# WM8904_mikroBUS_04.net
KiCad netlist of a schematic drawn in EasyEDA Pro
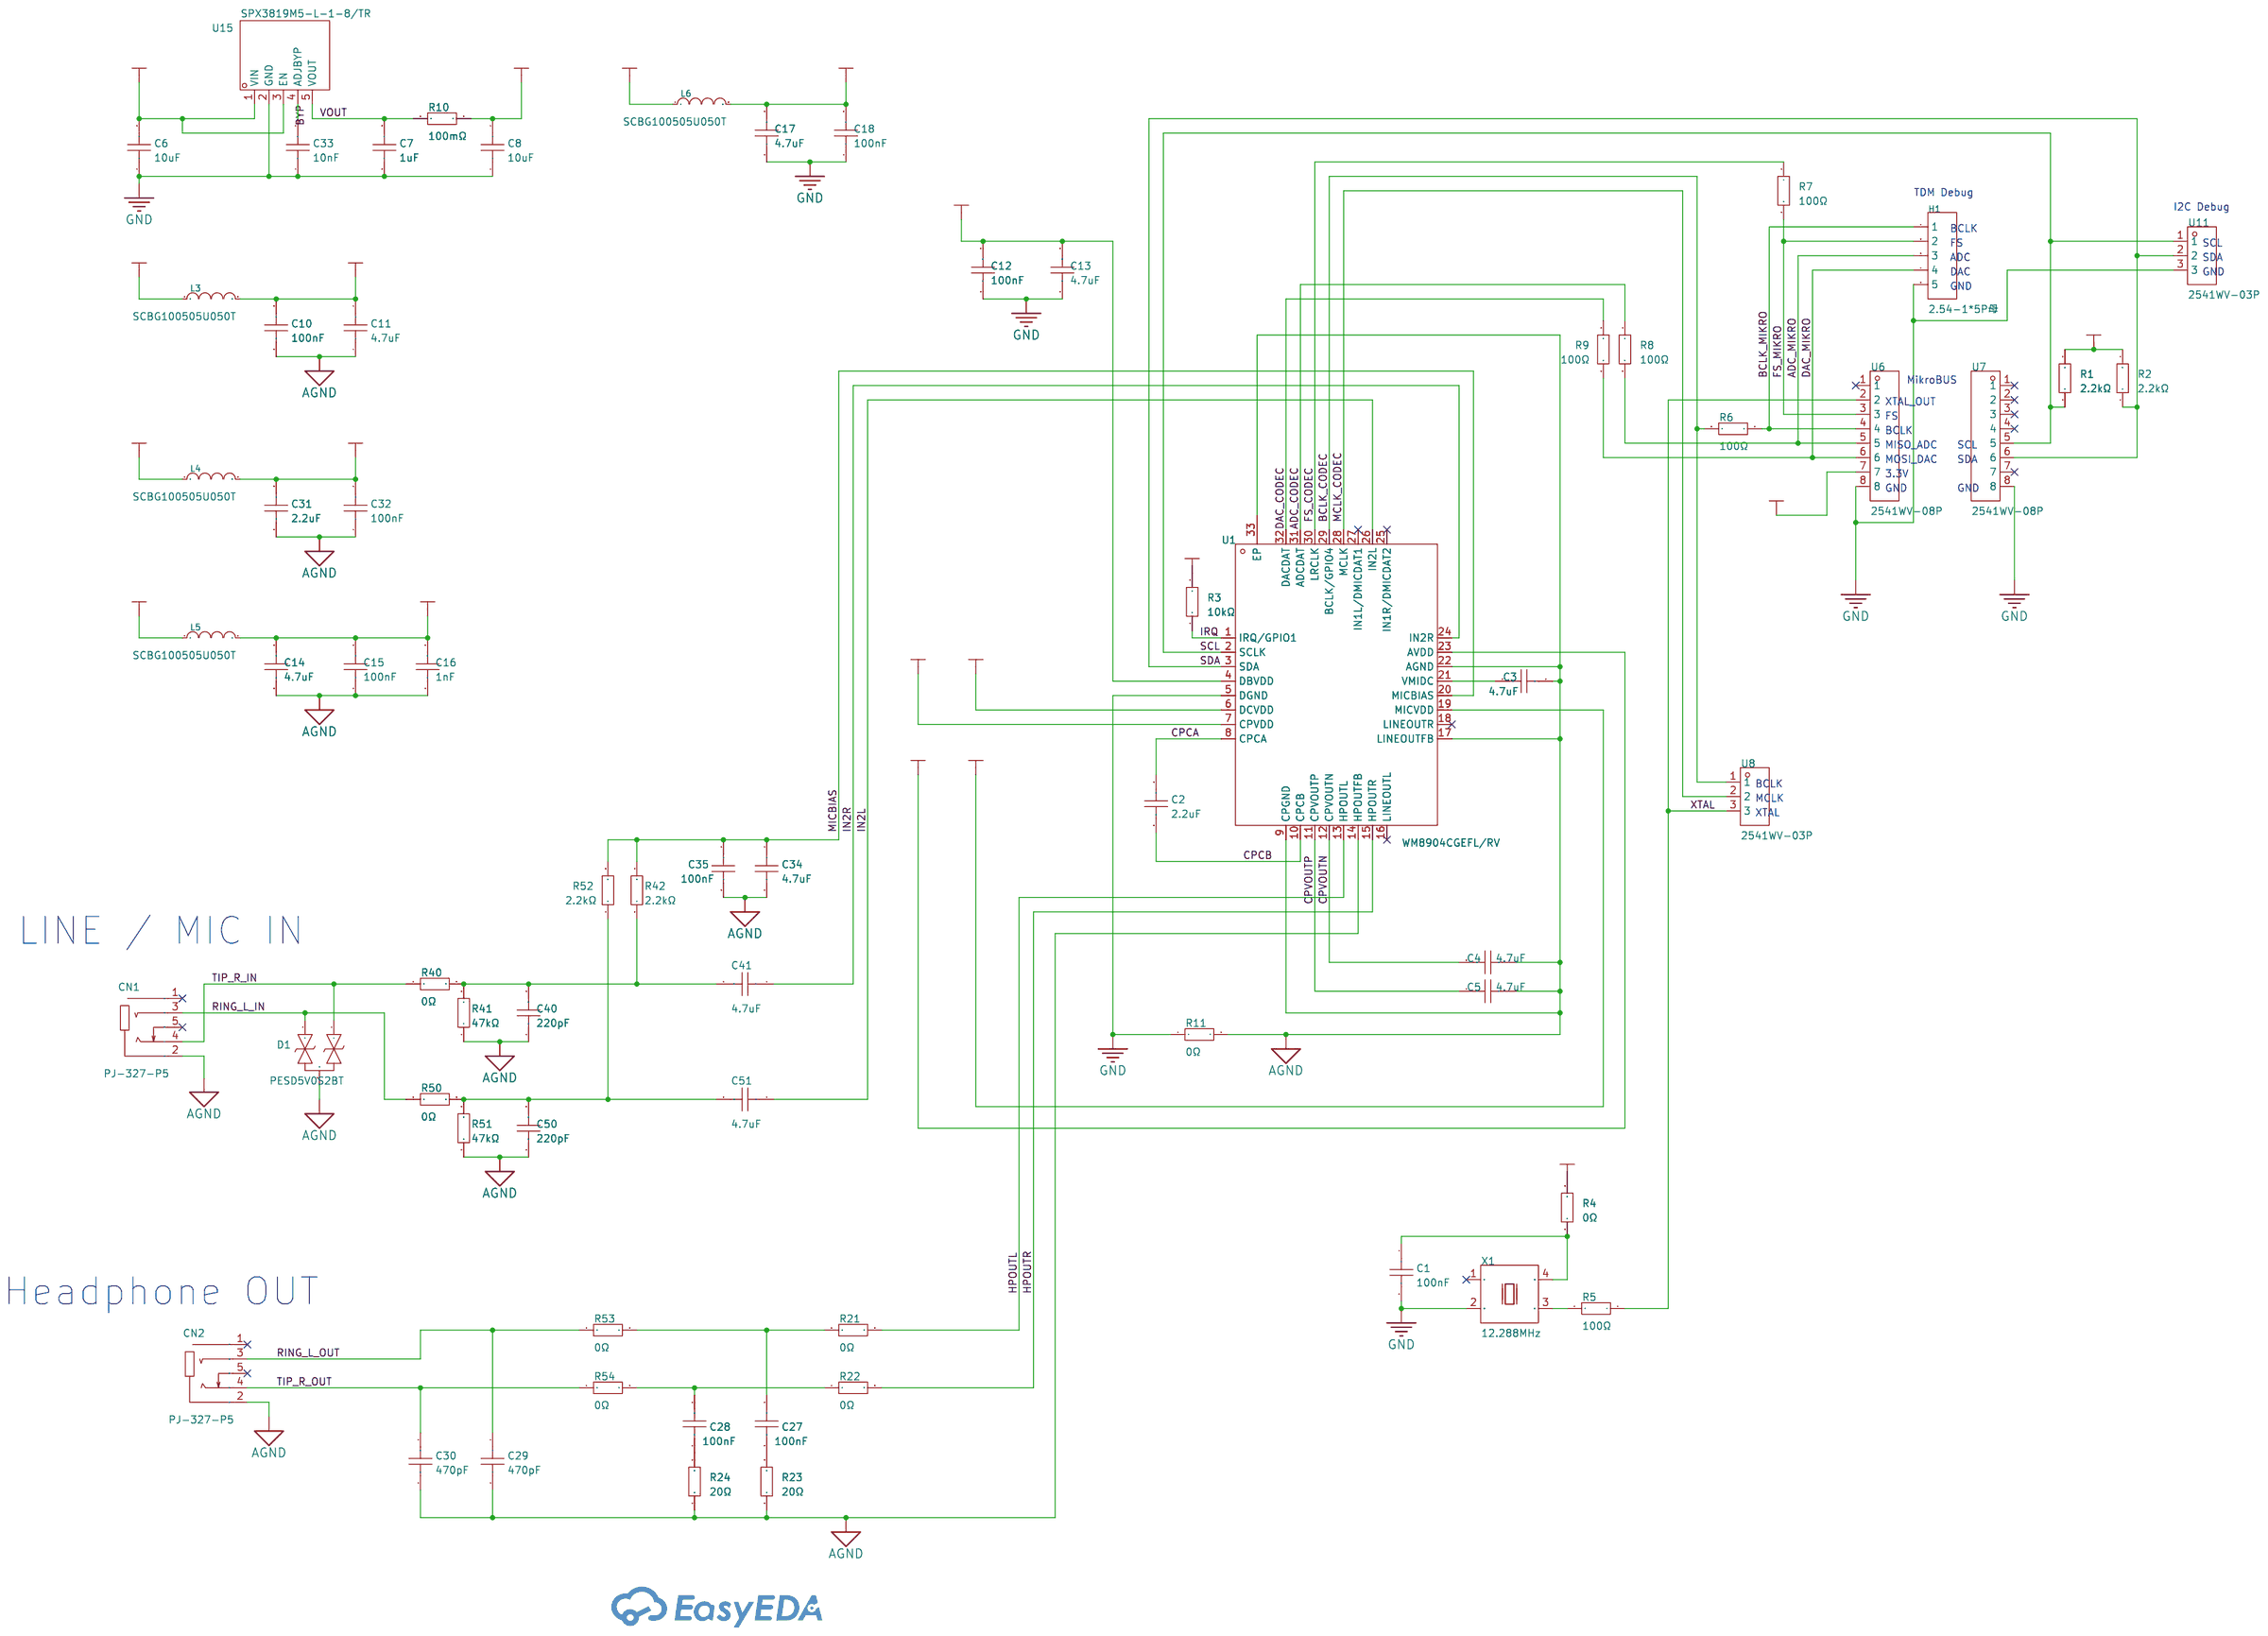
[diagram p0: schematic sheet]

(export (version "E")
  (design (tool "Eeschema 10.0.6"))
  (components
    (comp (ref "C1")
      (value "100nF")
      (footprint "easyedapro:C0603")
      (description "Capacitance:100nF Tolerance:±10% Tolerance:±10% Voltage Rating:50V Temperature Coefficient:X7R")
      (fields
        (field (name "Manufacturer Part") "CC0603KRX7R9BB104")
        (field (name "Manufacturer") "YAGEO(国巨)")
      )
      (libsource (lib "easyedapro") (part "CAP"))
    )
    (comp (ref "C2")
      (value "2.2uF")
      (footprint "easyedapro:C0603")
      (description "Capacitance:2.2uF Tolerance:±10% Tolerance:±10% Voltage Rating:16V Temperature Coefficient:X5R")
      (fields
        (field (name "Manufacturer Part") "CL10A225KO8NNNC")
        (field (name "Manufacturer") "SAMSUNG(三星)")
      )
      (libsource (lib "easyedapro") (part "CAP"))
    )
    (comp (ref "C3")
      (value "4.7uF")
      (footprint "easyedapro:C0603")
      (description "Capacitance:4.7uF Tolerance:±10% Tolerance:±10% Voltage Rating:16V Temperature Coefficient:X5R")
      (fields
        (field (name "Manufacturer Part") "CL10A475KO8NNNC")
        (field (name "Manufacturer") "SAMSUNG(三星)")
      )
      (libsource (lib "easyedapro") (part "CAP"))
    )
    (comp (ref "C4")
      (value "4.7uF")
      (footprint "easyedapro:C0603")
      (description "Capacitance:4.7uF Tolerance:±10% Tolerance:±10% Voltage Rating:16V Temperature Coefficient:X5R")
      (fields
        (field (name "Manufacturer Part") "CL10A475KO8NNNC")
        (field (name "Manufacturer") "SAMSUNG(三星)")
      )
      (libsource (lib "easyedapro") (part "CAP"))
    )
    (comp (ref "C5")
      (value "4.7uF")
      (footprint "easyedapro:C0603")
      (description "Capacitance:4.7uF Tolerance:±10% Tolerance:±10% Voltage Rating:16V Temperature Coefficient:X5R")
      (fields
        (field (name "Manufacturer Part") "CL10A475KO8NNNC")
        (field (name "Manufacturer") "SAMSUNG(三星)")
      )
      (libsource (lib "easyedapro") (part "CAP"))
    )
    (comp (ref "C6")
      (value "10uF")
      (footprint "easyedapro:C0603")
      (description "Capacitance:10uF Tolerance:±10% Tolerance:±10% Voltage Rating:10V Temperature Coefficient:X5R")
      (fields
        (field (name "Manufacturer Part") "CL10A106KP8NNNC")
        (field (name "Manufacturer") "SAMSUNG(三星)")
      )
      (libsource (lib "easyedapro") (part "CAP"))
    )
    (comp (ref "C7")
      (value "1uF")
      (footprint "easyedapro:C0603")
      (description "Capacitance:1uF Tolerance:±10% Tolerance:±10% Voltage Rating:50V Temperature Coefficient:X5R")
      (fields
        (field (name "Manufacturer Part") "CL10A105KB8NNNC")
        (field (name "Manufacturer") "SAMSUNG(三星)")
      )
      (libsource (lib "easyedapro") (part "CAP"))
    )
    (comp (ref "C8")
      (value "10uF")
      (footprint "easyedapro:C0603")
      (description "Capacitance:10uF Tolerance:±10% Tolerance:±10% Voltage Rating:10V Temperature Coefficient:X5R")
      (fields
        (field (name "Manufacturer Part") "CL10A106KP8NNNC")
        (field (name "Manufacturer") "SAMSUNG(三星)")
      )
      (libsource (lib "easyedapro") (part "CAP"))
    )
    (comp (ref "C10")
      (value "100nF")
      (footprint "easyedapro:C0603")
      (description "Capacitance:100nF Tolerance:±10% Tolerance:±10% Voltage Rating:50V Temperature Coefficient:X7R")
      (fields
        (field (name "Manufacturer Part") "CC0603KRX7R9BB104")
        (field (name "Manufacturer") "YAGEO(国巨)")
      )
      (libsource (lib "easyedapro") (part "CAP"))
    )
    (comp (ref "C11")
      (value "4.7uF")
      (footprint "easyedapro:C0603")
      (description "Capacitance:4.7uF Tolerance:±10% Tolerance:±10% Voltage Rating:16V Temperature Coefficient:X5R")
      (fields
        (field (name "Manufacturer Part") "CL10A475KO8NNNC")
        (field (name "Manufacturer") "SAMSUNG(三星)")
      )
      (libsource (lib "easyedapro") (part "CAP"))
    )
    (comp (ref "C12")
      (value "100nF")
      (footprint "easyedapro:C0603")
      (description "Capacitance:100nF Tolerance:±10% Tolerance:±10% Voltage Rating:50V Temperature Coefficient:X7R")
      (fields
        (field (name "Manufacturer Part") "CC0603KRX7R9BB104")
        (field (name "Manufacturer") "YAGEO(国巨)")
      )
      (libsource (lib "easyedapro") (part "CAP"))
    )
    (comp (ref "C13")
      (value "4.7uF")
      (footprint "easyedapro:C0603")
      (description "Capacitance:4.7uF Tolerance:±10% Tolerance:±10% Voltage Rating:16V Temperature Coefficient:X5R")
      (fields
        (field (name "Manufacturer Part") "CL10A475KO8NNNC")
        (field (name "Manufacturer") "SAMSUNG(三星)")
      )
      (libsource (lib "easyedapro") (part "CAP"))
    )
    (comp (ref "C14")
      (value "4.7uF")
      (footprint "easyedapro:C0603")
      (description "Capacitance:4.7uF Tolerance:±10% Tolerance:±10% Voltage Rating:16V Temperature Coefficient:X5R")
      (fields
        (field (name "Manufacturer Part") "CL10A475KO8NNNC")
        (field (name "Manufacturer") "SAMSUNG(三星)")
      )
      (libsource (lib "easyedapro") (part "CAP"))
    )
    (comp (ref "C15")
      (value "100nF")
      (footprint "easyedapro:C0603")
      (description "Capacitance:100nF Tolerance:±10% Tolerance:±10% Voltage Rating:50V Temperature Coefficient:X7R")
      (fields
        (field (name "Manufacturer Part") "CC0603KRX7R9BB104")
        (field (name "Manufacturer") "YAGEO(国巨)")
      )
      (libsource (lib "easyedapro") (part "CAP"))
    )
    (comp (ref "C16")
      (value "1nF")
      (footprint "easyedapro:C0603")
      (description "Capacitance:1nF Tolerance:±10% Tolerance:±10% Voltage Rating:50V Temperature Coefficient:X7R")
      (fields
        (field (name "Manufacturer Part") "CL10B102KB8NNNC")
        (field (name "Manufacturer") "SAMSUNG(三星)")
      )
      (libsource (lib "easyedapro") (part "CAP"))
    )
    (comp (ref "C17")
      (value "4.7uF")
      (footprint "easyedapro:C0603")
      (description "Capacitance:4.7uF Tolerance:±10% Tolerance:±10% Voltage Rating:16V Temperature Coefficient:X5R")
      (fields
        (field (name "Manufacturer Part") "CL10A475KO8NNNC")
        (field (name "Manufacturer") "SAMSUNG(三星)")
      )
      (libsource (lib "easyedapro") (part "CAP"))
    )
    (comp (ref "C18")
      (value "100nF")
      (footprint "easyedapro:C0603")
      (description "Capacitance:100nF Tolerance:±10% Tolerance:±10% Voltage Rating:50V Temperature Coefficient:X7R")
      (fields
        (field (name "Manufacturer Part") "CC0603KRX7R9BB104")
        (field (name "Manufacturer") "YAGEO(国巨)")
      )
      (libsource (lib "easyedapro") (part "CAP"))
    )
    (comp (ref "C27")
      (value "100nF")
      (footprint "easyedapro:C0603")
      (description "Capacitance:100nF Tolerance:±10% Tolerance:±10% Voltage Rating:50V Temperature Coefficient:X7R")
      (fields
        (field (name "Manufacturer Part") "CC0603KRX7R9BB104")
        (field (name "Manufacturer") "YAGEO(国巨)")
      )
      (libsource (lib "easyedapro") (part "CAP"))
    )
    (comp (ref "C28")
      (value "100nF")
      (footprint "easyedapro:C0603")
      (description "Capacitance:100nF Tolerance:±10% Tolerance:±10% Voltage Rating:50V Temperature Coefficient:X7R")
      (fields
        (field (name "Manufacturer Part") "CC0603KRX7R9BB104")
        (field (name "Manufacturer") "YAGEO(国巨)")
      )
      (libsource (lib "easyedapro") (part "CAP"))
    )
    (comp (ref "C29")
      (value "470pF")
      (footprint "easyedapro:C0603")
      (description "Capacitance:470pF Tolerance:±10% Tolerance:±10% Voltage Rating:50V Temperature Coefficient:X7R")
      (fields (field (name "Manufacturer Part") "0603B471K500NT") (field (name "Manufacturer") "FH(风华)"))
      (libsource (lib "easyedapro") (part "CAP"))
    )
    (comp (ref "C30")
      (value "470pF")
      (footprint "easyedapro:C0603")
      (description "Capacitance:470pF Tolerance:±10% Tolerance:±10% Voltage Rating:50V Temperature Coefficient:X7R")
      (fields (field (name "Manufacturer Part") "0603B471K500NT") (field (name "Manufacturer") "FH(风华)"))
      (libsource (lib "easyedapro") (part "CAP"))
    )
    (comp (ref "C31")
      (value "2.2uF")
      (footprint "easyedapro:C0603")
      (description "Capacitance:2.2uF Tolerance:±10% Tolerance:±10% Voltage Rating:16V Temperature Coefficient:X5R")
      (fields
        (field (name "Manufacturer Part") "CL10A225KO8NNNC")
        (field (name "Manufacturer") "SAMSUNG(三星)")
      )
      (libsource (lib "easyedapro") (part "CAP"))
    )
    (comp (ref "C32")
      (value "100nF")
      (footprint "easyedapro:C0603")
      (description "Capacitance:100nF Tolerance:±10% Tolerance:±10% Voltage Rating:50V Temperature Coefficient:X7R")
      (fields
        (field (name "Manufacturer Part") "CC0603KRX7R9BB104")
        (field (name "Manufacturer") "YAGEO(国巨)")
      )
      (libsource (lib "easyedapro") (part "CAP"))
    )
    (comp (ref "C33")
      (value "10nF")
      (footprint "easyedapro:C0603")
      (description "Capacitance:10nF Tolerance:±10% Tolerance:±10% Voltage Rating:50V Temperature Coefficient:X7R")
      (fields (field (name "Manufacturer Part") "0603B103K500NT") (field (name "Manufacturer") "FH(风华)"))
      (libsource (lib "easyedapro") (part "CAP"))
    )
    (comp (ref "C34")
      (value "4.7uF")
      (footprint "easyedapro:C0603")
      (description "Capacitance:4.7uF Tolerance:±10% Tolerance:±10% Voltage Rating:16V Temperature Coefficient:X5R")
      (fields
        (field (name "Manufacturer Part") "CL10A475KO8NNNC")
        (field (name "Manufacturer") "SAMSUNG(三星)")
      )
      (libsource (lib "easyedapro") (part "CAP"))
    )
    (comp (ref "C35")
      (value "100nF")
      (footprint "easyedapro:C0603")
      (description "Capacitance:100nF Tolerance:±10% Tolerance:±10% Voltage Rating:50V Temperature Coefficient:X7R")
      (fields
        (field (name "Manufacturer Part") "CC0603KRX7R9BB104")
        (field (name "Manufacturer") "YAGEO(国巨)")
      )
      (libsource (lib "easyedapro") (part "CAP"))
    )
    (comp (ref "C40")
      (value "220pF")
      (footprint "easyedapro:C0603")
      (description "Capacitance:220pF Tolerance:±10% Tolerance:±10% Voltage Rating:50V Temperature Coefficient:X7R")
      (fields
        (field (name "Manufacturer Part") "CL10B221KB8NNNC")
        (field (name "Manufacturer") "SAMSUNG(三星)")
      )
      (libsource (lib "easyedapro") (part "CAP"))
    )
    (comp (ref "C41")
      (value "4.7uF")
      (footprint "easyedapro:C0603")
      (description "Capacitance:4.7uF Tolerance:±10% Tolerance:±10% Voltage Rating:16V Temperature Coefficient:X5R")
      (fields
        (field (name "Manufacturer Part") "CL10A475KO8NNNC")
        (field (name "Manufacturer") "SAMSUNG(三星)")
      )
      (libsource (lib "easyedapro") (part "CAP"))
    )
    (comp (ref "C50")
      (value "220pF")
      (footprint "easyedapro:C0603")
      (description "Capacitance:220pF Tolerance:±10% Tolerance:±10% Voltage Rating:50V Temperature Coefficient:X7R")
      (fields
        (field (name "Manufacturer Part") "CL10B221KB8NNNC")
        (field (name "Manufacturer") "SAMSUNG(三星)")
      )
      (libsource (lib "easyedapro") (part "CAP"))
    )
    (comp (ref "C51")
      (value "4.7uF")
      (footprint "easyedapro:C0603")
      (description "Capacitance:4.7uF Tolerance:±10% Tolerance:±10% Voltage Rating:16V Temperature Coefficient:X5R")
      (fields
        (field (name "Manufacturer Part") "CL10A475KO8NNNC")
        (field (name "Manufacturer") "SAMSUNG(三星)")
      )
      (libsource (lib "easyedapro") (part "CAP"))
    )
    (comp (ref "CN1")
      (value "PJ-327-P5")
      (footprint "easyedapro:AUDIO-TH_PJ-327-P5")
      (fields (field (name "Manufacturer") "SOFNG(硕方)"))
      (libsource (lib "easyedapro") (part "PJ-327-P5"))
    )
    (comp (ref "CN2")
      (value "PJ-327-P5")
      (footprint "easyedapro:AUDIO-TH_PJ-327-P5")
      (fields (field (name "Manufacturer") "SOFNG(硕方)"))
      (libsource (lib "easyedapro") (part "PJ-327-P5"))
    )
    (comp (ref "D1")
      (value "PESD5V0S2BT")
      (footprint "easyedapro:SOT-23-3_L2.9-W1.3-P1.90-LS2.4-BR")
      (fields (field (name "Manufacturer") "GOODWORK(固得沃克)"))
      (libsource (lib "easyedapro") (part "PESD5V0S2BT_C28310457"))
    )
    (comp (ref "H1")
      (value "2.54-1*5P母")
      (footprint "easyedapro:HDR-TH_5P-P2.54-V-F")
      (fields (field (name "Manufacturer") "BOOMELE(博穆精密)"))
      (libsource (lib "easyedapro") (part "Header-Female-2.54_1x5"))
    )
    (comp (ref "L3")
      (value "SCBG100505U050T")
      (footprint "easyedapro:L0402")
      (fields (field (name "Manufacturer") "Yanchuang(研创)"))
      (libsource (lib "easyedapro") (part "SCBG100505U050T"))
    )
    (comp (ref "L4")
      (value "SCBG100505U050T")
      (footprint "easyedapro:L0402")
      (fields (field (name "Manufacturer") "Yanchuang(研创)"))
      (libsource (lib "easyedapro") (part "SCBG100505U050T"))
    )
    (comp (ref "L5")
      (value "SCBG100505U050T")
      (footprint "easyedapro:L0402")
      (fields (field (name "Manufacturer") "Yanchuang(研创)"))
      (libsource (lib "easyedapro") (part "SCBG100505U050T"))
    )
    (comp (ref "L6")
      (value "SCBG100505U050T")
      (footprint "easyedapro:L0402")
      (fields (field (name "Manufacturer") "Yanchuang(研创)"))
      (libsource (lib "easyedapro") (part "SCBG100505U050T"))
    )
    (comp (ref "R1")
      (value "2.2kΩ")
      (footprint "easyedapro:R0603")
      (fields
        (field (name "Manufacturer Part") "0603WAF2201T5E")
        (field (name "Manufacturer") "UNI-ROYAL(厚声)")
      )
      (libsource (lib "easyedapro") (part "Res"))
    )
    (comp (ref "R2")
      (value "2.2kΩ")
      (footprint "easyedapro:R0603")
      (fields
        (field (name "Manufacturer Part") "0603WAF2201T5E")
        (field (name "Manufacturer") "UNI-ROYAL(厚声)")
      )
      (libsource (lib "easyedapro") (part "Res"))
    )
    (comp (ref "R3")
      (value "10kΩ")
      (footprint "easyedapro:R0603")
      (fields
        (field (name "Manufacturer Part") "0603WAF1002T5E")
        (field (name "Manufacturer") "UNI-ROYAL(厚声)")
      )
      (libsource (lib "easyedapro") (part "Res"))
    )
    (comp (ref "R4")
      (value "0Ω")
      (footprint "easyedapro:R0603")
      (fields
        (field (name "Manufacturer Part") "0603WAF0000T5E")
        (field (name "Manufacturer") "UNI-ROYAL(厚声)")
      )
      (libsource (lib "easyedapro") (part "Res"))
    )
    (comp (ref "R5")
      (value "100Ω")
      (footprint "easyedapro:R0603")
      (fields
        (field (name "Manufacturer Part") "0603WAF1000T5E")
        (field (name "Manufacturer") "UNI-ROYAL(厚声)")
      )
      (libsource (lib "easyedapro") (part "Res"))
    )
    (comp (ref "R6")
      (value "100Ω")
      (footprint "easyedapro:R0603")
      (fields
        (field (name "Manufacturer Part") "0603WAF1000T5E")
        (field (name "Manufacturer") "UNI-ROYAL(厚声)")
      )
      (libsource (lib "easyedapro") (part "Res"))
    )
    (comp (ref "R7")
      (value "100Ω")
      (footprint "easyedapro:R0603")
      (fields
        (field (name "Manufacturer Part") "0603WAF1000T5E")
        (field (name "Manufacturer") "UNI-ROYAL(厚声)")
      )
      (libsource (lib "easyedapro") (part "Res"))
    )
    (comp (ref "R8")
      (value "100Ω")
      (footprint "easyedapro:R0603")
      (fields
        (field (name "Manufacturer Part") "0603WAF1000T5E")
        (field (name "Manufacturer") "UNI-ROYAL(厚声)")
      )
      (libsource (lib "easyedapro") (part "Res"))
    )
    (comp (ref "R9")
      (value "100Ω")
      (footprint "easyedapro:R0603")
      (fields
        (field (name "Manufacturer Part") "0603WAF1000T5E")
        (field (name "Manufacturer") "UNI-ROYAL(厚声)")
      )
      (libsource (lib "easyedapro") (part "Res"))
    )
    (comp (ref "R10")
      (value "100mΩ")
      (footprint "easyedapro:R0603")
      (fields
        (field (name "Manufacturer Part") "0603WAJ010KT5E")
        (field (name "Manufacturer") "UNI-ROYAL(厚声)")
      )
      (libsource (lib "easyedapro") (part "Res"))
    )
    (comp (ref "R11")
      (value "0Ω")
      (footprint "easyedapro:R0603")
      (fields
        (field (name "Manufacturer Part") "0603WAF0000T5E")
        (field (name "Manufacturer") "UNI-ROYAL(厚声)")
      )
      (libsource (lib "easyedapro") (part "Res"))
    )
    (comp (ref "R21")
      (value "0Ω")
      (footprint "easyedapro:R0603")
      (fields
        (field (name "Manufacturer Part") "0603WAF0000T5E")
        (field (name "Manufacturer") "UNI-ROYAL(厚声)")
      )
      (libsource (lib "easyedapro") (part "Res"))
    )
    (comp (ref "R22")
      (value "0Ω")
      (footprint "easyedapro:R0603")
      (fields
        (field (name "Manufacturer Part") "0603WAF0000T5E")
        (field (name "Manufacturer") "UNI-ROYAL(厚声)")
      )
      (libsource (lib "easyedapro") (part "Res"))
    )
    (comp (ref "R23")
      (value "20Ω")
      (footprint "easyedapro:R0603")
      (fields
        (field (name "Manufacturer Part") "0603WAF200JT5E")
        (field (name "Manufacturer") "UNI-ROYAL(厚声)")
      )
      (libsource (lib "easyedapro") (part "Res"))
    )
    (comp (ref "R24")
      (value "20Ω")
      (footprint "easyedapro:R0603")
      (fields
        (field (name "Manufacturer Part") "0603WAF200JT5E")
        (field (name "Manufacturer") "UNI-ROYAL(厚声)")
      )
      (libsource (lib "easyedapro") (part "Res"))
    )
    (comp (ref "R40")
      (value "0Ω")
      (footprint "easyedapro:R0603")
      (fields
        (field (name "Manufacturer Part") "0603WAF0000T5E")
        (field (name "Manufacturer") "UNI-ROYAL(厚声)")
      )
      (libsource (lib "easyedapro") (part "Res"))
    )
    (comp (ref "R41")
      (value "47kΩ")
      (footprint "easyedapro:R0603")
      (fields
        (field (name "Manufacturer Part") "0603WAF4702T5E")
        (field (name "Manufacturer") "UNI-ROYAL(厚声)")
      )
      (libsource (lib "easyedapro") (part "Res"))
    )
    (comp (ref "R42")
      (value "2.2kΩ")
      (footprint "easyedapro:R0603")
      (fields
        (field (name "Manufacturer Part") "0603WAF2201T5E")
        (field (name "Manufacturer") "UNI-ROYAL(厚声)")
      )
      (libsource (lib "easyedapro") (part "Res"))
    )
    (comp (ref "R50")
      (value "0Ω")
      (footprint "easyedapro:R0603")
      (fields
        (field (name "Manufacturer Part") "0603WAF0000T5E")
        (field (name "Manufacturer") "UNI-ROYAL(厚声)")
      )
      (libsource (lib "easyedapro") (part "Res"))
    )
    (comp (ref "R51")
      (value "47kΩ")
      (footprint "easyedapro:R0603")
      (fields
        (field (name "Manufacturer Part") "0603WAF4702T5E")
        (field (name "Manufacturer") "UNI-ROYAL(厚声)")
      )
      (libsource (lib "easyedapro") (part "Res"))
    )
    (comp (ref "R52")
      (value "2.2kΩ")
      (footprint "easyedapro:R0603")
      (fields
        (field (name "Manufacturer Part") "0603WAF2201T5E")
        (field (name "Manufacturer") "UNI-ROYAL(厚声)")
      )
      (libsource (lib "easyedapro") (part "Res"))
    )
    (comp (ref "R53")
      (value "0Ω")
      (footprint "easyedapro:R0603")
      (fields
        (field (name "Manufacturer Part") "0603WAF0000T5E")
        (field (name "Manufacturer") "UNI-ROYAL(厚声)")
      )
      (libsource (lib "easyedapro") (part "Res"))
    )
    (comp (ref "R54")
      (value "0Ω")
      (footprint "easyedapro:R0603")
      (fields
        (field (name "Manufacturer Part") "0603WAF0000T5E")
        (field (name "Manufacturer") "UNI-ROYAL(厚声)")
      )
      (libsource (lib "easyedapro") (part "Res"))
    )
    (comp (ref "U1")
      (value "WM8904CGEFL/RV")
      (footprint "easyedapro:QFN-32_L4.0-W4.0-P0.40-BL-EP2.7")
      (fields (field (name "Manufacturer") "Cirrus Logic(凌云)"))
      (libsource (lib "easyedapro") (part "WM8904CGEFL/RV"))
    )
    (comp (ref "U6")
      (value "2541WV-08P")
      (footprint "easyedapro:HDR-TH_8P-P2.54-V-M-4")
      (fields (field (name "Manufacturer") "HanElectricity(瀚源)"))
      (libsource (lib "easyedapro") (part "2541WV-08P"))
    )
    (comp (ref "U7")
      (value "2541WV-08P")
      (footprint "easyedapro:HDR-TH_8P-P2.54-V-M-4")
      (fields (field (name "Manufacturer") "HanElectricity(瀚源)"))
      (libsource (lib "easyedapro") (part "2541WV-08P"))
    )
    (comp (ref "U8")
      (value "2541WV-03P")
      (footprint "easyedapro:HDR-TH_3P-P2.54-V-M-2")
      (fields (field (name "Manufacturer") "HanElectricity(瀚源)"))
      (libsource (lib "easyedapro") (part "2541WV-03P"))
    )
    (comp (ref "U11")
      (value "2541WV-03P")
      (footprint "easyedapro:HDR-TH_3P-P2.54-V-M-2")
      (fields (field (name "Manufacturer") "HanElectricity(瀚源)"))
      (libsource (lib "easyedapro") (part "2541WV-03P"))
    )
    (comp (ref "U15")
      (value "SPX3819M5-L-1-8/TR")
      (footprint "easyedapro:SOT-23-5_L3.0-W1.7-P0.95-LS2.8-TL")
      (fields (field (name "Manufacturer") "MaxLinear(迈凌)"))
      (libsource (lib "easyedapro") (part "SPX3819M5-L-1-8"))
    )
    (comp (ref "X1")
      (value "12.288MHz")
      (footprint "easyedapro:OSC-SMD_4P-L2.5-W2.0-BL")
      (fields (field (name "Manufacturer Part") "X1G0041710019") (field (name "Manufacturer") "EPSON(爱普生)"))
      (libsource (lib "easyedapro") (part "X1G004171001900"))
    )
  )
  (nets
    (net (code "1") (name "+3.3V") (class "Default")
      (node (ref "C12") (pin "2") (pinfunction "2_2") (pintype "input"))
      (node (ref "C13") (pin "2") (pinfunction "2_2") (pintype "input"))
      (node (ref "C6") (pin "2") (pinfunction "2_2") (pintype "input"))
      (node (ref "L3") (pin "1") (pinfunction "1_1") (pintype "input"))
      (node (ref "R1") (pin "2") (pinfunction "2_2") (pintype "input"))
      (node (ref "R2") (pin "2") (pinfunction "2_2") (pintype "input"))
      (node (ref "R3") (pin "2") (pinfunction "2_2") (pintype "input"))
      (node (ref "R4") (pin "2") (pinfunction "2_2") (pintype "input"))
      (node (ref "U1") (pin "4") (pinfunction "DBVDD_4") (pintype "unspecified"))
      (node (ref "U15") (pin "1") (pinfunction "VIN_1") (pintype "unspecified"))
      (node (ref "U15") (pin "3") (pinfunction "EN_3") (pintype "unspecified"))
      (node (ref "U6") (pin "7") (pinfunction "7_7") (pintype "unspecified"))
    )
    (net (code "2") (name "/ADC_CODEC") (class "Default")
      (node (ref "R8") (pin "1") (pinfunction "1_1") (pintype "input"))
      (node (ref "U1") (pin "31") (pinfunction "ADCDAT_31") (pintype "unspecified"))
    )
    (net (code "3") (name "/ADC_MIKRO") (class "Default")
      (node (ref "H1") (pin "3") (pinfunction "3_3") (pintype "input"))
      (node (ref "R8") (pin "2") (pinfunction "2_2") (pintype "input"))
      (node (ref "U6") (pin "5") (pinfunction "5_5") (pintype "unspecified"))
    )
    (net (code "4") (name "/BCLK_CODEC") (class "Default")
      (node (ref "R6") (pin "2") (pinfunction "2_2") (pintype "input"))
      (node (ref "U1") (pin "29") (pinfunction "BCLK/GPIO4_29") (pintype "unspecified"))
      (node (ref "U8") (pin "1") (pinfunction "1_1") (pintype "unspecified"))
    )
    (net (code "5") (name "/BCLK_MIKRO") (class "Default")
      (node (ref "H1") (pin "1") (pinfunction "1_1") (pintype "input"))
      (node (ref "R6") (pin "1") (pinfunction "1_1") (pintype "input"))
      (node (ref "U6") (pin "4") (pinfunction "4_4") (pintype "unspecified"))
    )
    (net (code "6") (name "/BYP") (class "Default")
      (node (ref "C33") (pin "2") (pinfunction "2_2") (pintype "input"))
      (node (ref "U15") (pin "4") (pinfunction "ADJBYP_4") (pintype "unspecified"))
    )
    (net (code "7") (name "/CPCA") (class "Default")
      (node (ref "C2") (pin "1") (pinfunction "1_1") (pintype "input"))
      (node (ref "U1") (pin "8") (pinfunction "CPCA_8") (pintype "unspecified"))
    )
    (net (code "8") (name "/CPCB") (class "Default")
      (node (ref "C2") (pin "2") (pinfunction "2_2") (pintype "input"))
      (node (ref "U1") (pin "10") (pinfunction "CPCB_10") (pintype "unspecified"))
    )
    (net (code "9") (name "/CPVOUTN") (class "Default")
      (node (ref "C4") (pin "2") (pinfunction "2_2") (pintype "input"))
      (node (ref "U1") (pin "12") (pinfunction "CPVOUTN_12") (pintype "unspecified"))
    )
    (net (code "10") (name "/CPVOUTP") (class "Default")
      (node (ref "C5") (pin "2") (pinfunction "2_2") (pintype "input"))
      (node (ref "U1") (pin "11") (pinfunction "CPVOUTP_11") (pintype "unspecified"))
    )
    (net (code "11") (name "/DAC_CODEC") (class "Default")
      (node (ref "R9") (pin "1") (pinfunction "1_1") (pintype "input"))
      (node (ref "U1") (pin "32") (pinfunction "DACDAT_32") (pintype "unspecified"))
    )
    (net (code "12") (name "/DAC_MIKRO") (class "Default")
      (node (ref "H1") (pin "4") (pinfunction "4_4") (pintype "input"))
      (node (ref "R9") (pin "2") (pinfunction "2_2") (pintype "input"))
      (node (ref "U6") (pin "6") (pinfunction "6_6") (pintype "unspecified"))
    )
    (net (code "13") (name "/FS_CODEC") (class "Default")
      (node (ref "R7") (pin "1") (pinfunction "1_1") (pintype "input"))
      (node (ref "U1") (pin "30") (pinfunction "LRCLK_30") (pintype "unspecified"))
    )
    (net (code "14") (name "/FS_MIKRO") (class "Default")
      (node (ref "H1") (pin "2") (pinfunction "2_2") (pintype "input"))
      (node (ref "R7") (pin "2") (pinfunction "2_2") (pintype "input"))
      (node (ref "U6") (pin "3") (pinfunction "3_3") (pintype "unspecified"))
    )
    (net (code "15") (name "/HPOUTL") (class "Default")
      (node (ref "R21") (pin "2") (pinfunction "2_2") (pintype "input"))
      (node (ref "U1") (pin "13") (pinfunction "HPOUTL_13") (pintype "unspecified"))
    )
    (net (code "16") (name "/HPOUTR") (class "Default")
      (node (ref "R22") (pin "2") (pinfunction "2_2") (pintype "input"))
      (node (ref "U1") (pin "15") (pinfunction "HPOUTR_15") (pintype "unspecified"))
    )
    (net (code "17") (name "/IN2L") (class "Default")
      (node (ref "C51") (pin "1") (pinfunction "1_1") (pintype "input"))
      (node (ref "U1") (pin "26") (pinfunction "IN2L_26") (pintype "unspecified"))
    )
    (net (code "18") (name "/IN2R") (class "Default")
      (node (ref "C41") (pin "1") (pinfunction "1_1") (pintype "input"))
      (node (ref "U1") (pin "24") (pinfunction "IN2R_24") (pintype "unspecified"))
    )
    (net (code "19") (name "/IRQ") (class "Default")
      (node (ref "R3") (pin "1") (pinfunction "1_1") (pintype "input"))
      (node (ref "U1") (pin "1") (pinfunction "IRQ/GPIO1_1") (pintype "unspecified"))
    )
    (net (code "20") (name "/MCLK_CODEC") (class "Default")
      (node (ref "U1") (pin "28") (pinfunction "MCLK_28") (pintype "unspecified"))
      (node (ref "U8") (pin "2") (pinfunction "2_2") (pintype "unspecified"))
    )
    (net (code "21") (name "/MICBIAS") (class "Default")
      (node (ref "C34") (pin "1") (pinfunction "1_1") (pintype "input"))
      (node (ref "C35") (pin "1") (pinfunction "1_1") (pintype "input"))
      (node (ref "R42") (pin "2") (pinfunction "2_2") (pintype "input"))
      (node (ref "R52") (pin "2") (pinfunction "2_2") (pintype "input"))
      (node (ref "U1") (pin "20") (pinfunction "MICBIAS_20") (pintype "unspecified"))
    )
    (net (code "22") (name "/RING_L_IN") (class "Default")
      (node (ref "CN1") (pin "3") (pinfunction "3_3") (pintype "unspecified"))
      (node (ref "D1") (pin "2") (pinfunction "2_2") (pintype "unspecified"))
      (node (ref "R50") (pin "1") (pinfunction "1_1") (pintype "input"))
    )
    (net (code "23") (name "/RING_L_OUT") (class "Default")
      (node (ref "C29") (pin "1") (pinfunction "1_1") (pintype "input"))
      (node (ref "CN2") (pin "3") (pinfunction "3_3") (pintype "unspecified"))
      (node (ref "R53") (pin "1") (pinfunction "1_1") (pintype "input"))
    )
    (net (code "24") (name "/SCL") (class "Default")
      (node (ref "R1") (pin "1") (pinfunction "1_1") (pintype "input"))
      (node (ref "U1") (pin "2") (pinfunction "SCLK_2") (pintype "unspecified"))
      (node (ref "U11") (pin "1") (pinfunction "1_1") (pintype "unspecified"))
      (node (ref "U7") (pin "5") (pinfunction "5_5") (pintype "unspecified"))
    )
    (net (code "25") (name "/SDA") (class "Default")
      (node (ref "R2") (pin "1") (pinfunction "1_1") (pintype "input"))
      (node (ref "U1") (pin "3") (pinfunction "SDA_3") (pintype "unspecified"))
      (node (ref "U11") (pin "2") (pinfunction "2_2") (pintype "unspecified"))
      (node (ref "U7") (pin "6") (pinfunction "6_6") (pintype "unspecified"))
    )
    (net (code "26") (name "/TIP_R_IN") (class "Default")
      (node (ref "CN1") (pin "4") (pinfunction "4_4") (pintype "unspecified"))
      (node (ref "D1") (pin "1") (pinfunction "1_1") (pintype "unspecified"))
      (node (ref "R40") (pin "1") (pinfunction "1_1") (pintype "input"))
    )
    (net (code "27") (name "/TIP_R_OUT") (class "Default")
      (node (ref "C30") (pin "1") (pinfunction "1_1") (pintype "input"))
      (node (ref "CN2") (pin "4") (pinfunction "4_4") (pintype "unspecified"))
      (node (ref "R54") (pin "1") (pinfunction "1_1") (pintype "input"))
    )
    (net (code "28") (name "/VOUT") (class "Default")
      (node (ref "C7") (pin "2") (pinfunction "2_2") (pintype "input"))
      (node (ref "R10") (pin "1") (pinfunction "1_1") (pintype "input"))
      (node (ref "U15") (pin "5") (pinfunction "VOUT_5") (pintype "unspecified"))
    )
    (net (code "29") (name "/XTAL") (class "Default")
      (node (ref "R5") (pin "1") (pinfunction "1_1") (pintype "input"))
      (node (ref "U6") (pin "2") (pinfunction "2_2") (pintype "unspecified"))
      (node (ref "U8") (pin "3") (pinfunction "3_3") (pintype "unspecified"))
    )
    (net (code "30") (name "AGND") (class "Default")
      (node (ref "C10") (pin "1") (pinfunction "1_1") (pintype "input"))
      (node (ref "C11") (pin "1") (pinfunction "1_1") (pintype "input"))
      (node (ref "C14") (pin "1") (pinfunction "1_1") (pintype "input"))
      (node (ref "C15") (pin "1") (pinfunction "1_1") (pintype "input"))
      (node (ref "C16") (pin "1") (pinfunction "1_1") (pintype "input"))
      (node (ref "C29") (pin "2") (pinfunction "2_2") (pintype "input"))
      (node (ref "C3") (pin "2") (pinfunction "2_2") (pintype "input"))
      (node (ref "C30") (pin "2") (pinfunction "2_2") (pintype "input"))
      (node (ref "C31") (pin "1") (pinfunction "1_1") (pintype "input"))
      (node (ref "C32") (pin "1") (pinfunction "1_1") (pintype "input"))
      (node (ref "C34") (pin "2") (pinfunction "2_2") (pintype "input"))
      (node (ref "C35") (pin "2") (pinfunction "2_2") (pintype "input"))
      (node (ref "C4") (pin "1") (pinfunction "1_1") (pintype "input"))
      (node (ref "C40") (pin "1") (pinfunction "1_1") (pintype "input"))
      (node (ref "C5") (pin "1") (pinfunction "1_1") (pintype "input"))
      (node (ref "C50") (pin "1") (pinfunction "1_1") (pintype "input"))
      (node (ref "CN1") (pin "2") (pinfunction "2_2") (pintype "unspecified"))
      (node (ref "CN2") (pin "2") (pinfunction "2_2") (pintype "unspecified"))
      (node (ref "D1") (pin "3") (pinfunction "3_3") (pintype "unspecified"))
      (node (ref "R11") (pin "2") (pinfunction "2_2") (pintype "input"))
      (node (ref "R23") (pin "1") (pinfunction "1_1") (pintype "input"))
      (node (ref "R24") (pin "1") (pinfunction "1_1") (pintype "input"))
      (node (ref "R41") (pin "1") (pinfunction "1_1") (pintype "input"))
      (node (ref "R51") (pin "1") (pinfunction "1_1") (pintype "input"))
      (node (ref "U1") (pin "14") (pinfunction "HPOUTFB_14") (pintype "unspecified"))
      (node (ref "U1") (pin "17") (pinfunction "LINEOUTFB_17") (pintype "unspecified"))
      (node (ref "U1") (pin "22") (pinfunction "AGND_22") (pintype "unspecified"))
      (node (ref "U1") (pin "33") (pinfunction "EP_33") (pintype "unspecified"))
      (node (ref "U1") (pin "9") (pinfunction "CPGND_9") (pintype "unspecified"))
    )
    (net (code "31") (name "AVDD") (class "Default")
      (node (ref "C31") (pin "2") (pinfunction "2_2") (pintype "input"))
      (node (ref "C32") (pin "2") (pinfunction "2_2") (pintype "input"))
      (node (ref "L4") (pin "2") (pinfunction "2_2") (pintype "input"))
      (node (ref "U1") (pin "23") (pinfunction "AVDD_23") (pintype "unspecified"))
    )
    (net (code "32") (name "CPVDD") (class "Default")
      (node (ref "C14") (pin "2") (pinfunction "2_2") (pintype "input"))
      (node (ref "C15") (pin "2") (pinfunction "2_2") (pintype "input"))
      (node (ref "C16") (pin "2") (pinfunction "2_2") (pintype "input"))
      (node (ref "L5") (pin "2") (pinfunction "2_2") (pintype "input"))
      (node (ref "U1") (pin "7") (pinfunction "CPVDD_7") (pintype "unspecified"))
    )
    (net (code "33") (name "DCVDD") (class "Default")
      (node (ref "C17") (pin "2") (pinfunction "2_2") (pintype "input"))
      (node (ref "C18") (pin "2") (pinfunction "2_2") (pintype "input"))
      (node (ref "L6") (pin "2") (pinfunction "2_2") (pintype "input"))
      (node (ref "U1") (pin "6") (pinfunction "DCVDD_6") (pintype "unspecified"))
    )
    (net (code "34") (name "GND") (class "Default")
      (node (ref "C1") (pin "2") (pinfunction "2_2") (pintype "input"))
      (node (ref "C12") (pin "1") (pinfunction "1_1") (pintype "input"))
      (node (ref "C13") (pin "1") (pinfunction "1_1") (pintype "input"))
      (node (ref "C17") (pin "1") (pinfunction "1_1") (pintype "input"))
      (node (ref "C18") (pin "1") (pinfunction "1_1") (pintype "input"))
      (node (ref "C33") (pin "1") (pinfunction "1_1") (pintype "input"))
      (node (ref "C6") (pin "1") (pinfunction "1_1") (pintype "input"))
      (node (ref "C7") (pin "1") (pinfunction "1_1") (pintype "input"))
      (node (ref "C8") (pin "1") (pinfunction "1_1") (pintype "input"))
      (node (ref "H1") (pin "5") (pinfunction "5_5") (pintype "input"))
      (node (ref "R11") (pin "1") (pinfunction "1_1") (pintype "input"))
      (node (ref "U1") (pin "5") (pinfunction "DGND_5") (pintype "unspecified"))
      (node (ref "U11") (pin "3") (pinfunction "3_3") (pintype "unspecified"))
      (node (ref "U15") (pin "2") (pinfunction "GND_2") (pintype "unspecified"))
      (node (ref "U6") (pin "8") (pinfunction "8_8") (pintype "unspecified"))
      (node (ref "U7") (pin "8") (pinfunction "8_8") (pintype "unspecified"))
      (node (ref "X1") (pin "2") (pinfunction "GND_2") (pintype "unspecified"))
    )
    (net (code "35") (name "MICVDD") (class "Default")
      (node (ref "C10") (pin "2") (pinfunction "2_2") (pintype "input"))
      (node (ref "C11") (pin "2") (pinfunction "2_2") (pintype "input"))
      (node (ref "L3") (pin "2") (pinfunction "2_2") (pintype "input"))
      (node (ref "U1") (pin "19") (pinfunction "MICVDD_19") (pintype "unspecified"))
    )
    (net (code "36") (name "Net-(C27-Pad1)") (class "Default")
      (node (ref "C27") (pin "1") (pinfunction "1_1") (pintype "input"))
      (node (ref "R21") (pin "1") (pinfunction "1_1") (pintype "input"))
      (node (ref "R53") (pin "2") (pinfunction "2_2") (pintype "input"))
    )
    (net (code "37") (name "Net-(C27-Pad2)") (class "Default")
      (node (ref "C27") (pin "2") (pinfunction "2_2") (pintype "input"))
      (node (ref "R23") (pin "2") (pinfunction "2_2") (pintype "input"))
    )
    (net (code "38") (name "Net-(C28-Pad1)") (class "Default")
      (node (ref "C28") (pin "1") (pinfunction "1_1") (pintype "input"))
      (node (ref "R22") (pin "1") (pinfunction "1_1") (pintype "input"))
      (node (ref "R54") (pin "2") (pinfunction "2_2") (pintype "input"))
    )
    (net (code "39") (name "Net-(C28-Pad2)") (class "Default")
      (node (ref "C28") (pin "2") (pinfunction "2_2") (pintype "input"))
      (node (ref "R24") (pin "2") (pinfunction "2_2") (pintype "input"))
    )
    (net (code "40") (name "Net-(C40-Pad2)") (class "Default")
      (node (ref "C40") (pin "2") (pinfunction "2_2") (pintype "input"))
      (node (ref "C41") (pin "2") (pinfunction "2_2") (pintype "input"))
      (node (ref "R40") (pin "2") (pinfunction "2_2") (pintype "input"))
      (node (ref "R41") (pin "2") (pinfunction "2_2") (pintype "input"))
      (node (ref "R42") (pin "1") (pinfunction "1_1") (pintype "input"))
    )
    (net (code "41") (name "Net-(C50-Pad2)") (class "Default")
      (node (ref "C50") (pin "2") (pinfunction "2_2") (pintype "input"))
      (node (ref "C51") (pin "2") (pinfunction "2_2") (pintype "input"))
      (node (ref "R50") (pin "2") (pinfunction "2_2") (pintype "input"))
      (node (ref "R51") (pin "2") (pinfunction "2_2") (pintype "input"))
      (node (ref "R52") (pin "1") (pinfunction "1_1") (pintype "input"))
    )
    (net (code "42") (name "Net-(U1-VMIDC)") (class "Default")
      (node (ref "C3") (pin "1") (pinfunction "1_1") (pintype "input"))
      (node (ref "U1") (pin "21") (pinfunction "VMIDC_21") (pintype "unspecified"))
    )
    (net (code "43") (name "Net-(X1-OUT)") (class "Default")
      (node (ref "R5") (pin "2") (pinfunction "2_2") (pintype "input"))
      (node (ref "X1") (pin "3") (pinfunction "OUT_3") (pintype "unspecified"))
    )
    (net (code "44") (name "Net-(X1-VDD)") (class "Default")
      (node (ref "C1") (pin "1") (pinfunction "1_1") (pintype "input"))
      (node (ref "R4") (pin "1") (pinfunction "1_1") (pintype "input"))
      (node (ref "X1") (pin "4") (pinfunction "VDD_4") (pintype "unspecified"))
    )
    (net (code "45") (name "VCC_P1V8") (class "Default")
      (node (ref "C8") (pin "2") (pinfunction "2_2") (pintype "input"))
      (node (ref "L4") (pin "1") (pinfunction "1_1") (pintype "input"))
      (node (ref "L5") (pin "1") (pinfunction "1_1") (pintype "input"))
      (node (ref "L6") (pin "1") (pinfunction "1_1") (pintype "input"))
      (node (ref "R10") (pin "2") (pinfunction "2_2") (pintype "input"))
    )
    (net (code "46") (name "unconnected-(CN1-Pad1)") (class "Default")
      (node (ref "CN1") (pin "1") (pinfunction "1_1") (pintype "unspecified+no_connect"))
    )
    (net (code "47") (name "unconnected-(CN1-Pad5)") (class "Default")
      (node (ref "CN1") (pin "5") (pinfunction "5_5") (pintype "unspecified+no_connect"))
    )
    (net (code "48") (name "unconnected-(CN2-Pad1)") (class "Default")
      (node (ref "CN2") (pin "1") (pinfunction "1_1") (pintype "unspecified+no_connect"))
    )
    (net (code "49") (name "unconnected-(CN2-Pad5)") (class "Default")
      (node (ref "CN2") (pin "5") (pinfunction "5_5") (pintype "unspecified+no_connect"))
    )
    (net (code "50") (name "unconnected-(U1-IN1L{slash}DMICDAT1-Pad27)") (class "Default")
      (node (ref "U1") (pin "27") (pinfunction "IN1L/DMICDAT1_27") (pintype "unspecified+no_connect"))
    )
    (net (code "51") (name "unconnected-(U1-IN1R{slash}DMICDAT2-Pad25)") (class "Default")
      (node (ref "U1") (pin "25") (pinfunction "IN1R/DMICDAT2_25") (pintype "unspecified+no_connect"))
    )
    (net (code "52") (name "unconnected-(U1-LINEOUTL-Pad16)") (class "Default")
      (node (ref "U1") (pin "16") (pinfunction "LINEOUTL_16") (pintype "unspecified+no_connect"))
    )
    (net (code "53") (name "unconnected-(U1-LINEOUTR-Pad18)") (class "Default")
      (node (ref "U1") (pin "18") (pinfunction "LINEOUTR_18") (pintype "unspecified+no_connect"))
    )
    (net (code "54") (name "unconnected-(U6-Pad1)") (class "Default")
      (node (ref "U6") (pin "1") (pinfunction "1_1") (pintype "unspecified+no_connect"))
    )
    (net (code "55") (name "unconnected-(U7-Pad1)") (class "Default")
      (node (ref "U7") (pin "1") (pinfunction "1_1") (pintype "unspecified+no_connect"))
    )
    (net (code "56") (name "unconnected-(U7-Pad2)") (class "Default")
      (node (ref "U7") (pin "2") (pinfunction "2_2") (pintype "unspecified+no_connect"))
    )
    (net (code "57") (name "unconnected-(U7-Pad3)") (class "Default")
      (node (ref "U7") (pin "3") (pinfunction "3_3") (pintype "unspecified+no_connect"))
    )
    (net (code "58") (name "unconnected-(U7-Pad4)") (class "Default")
      (node (ref "U7") (pin "4") (pinfunction "4_4") (pintype "unspecified+no_connect"))
    )
    (net (code "59") (name "unconnected-(U7-Pad7)") (class "Default")
      (node (ref "U7") (pin "7") (pinfunction "7_7") (pintype "unspecified+no_connect"))
    )
    (net (code "60") (name "unconnected-(X1-{slash}ST-Pad1)") (class "Default")
      (node (ref "X1") (pin "1") (pinfunction "/ST_1") (pintype "unspecified+no_connect"))
    )
  )
)
